# MCU.net
KiCad netlist of a schematic drawn in Altium Designer
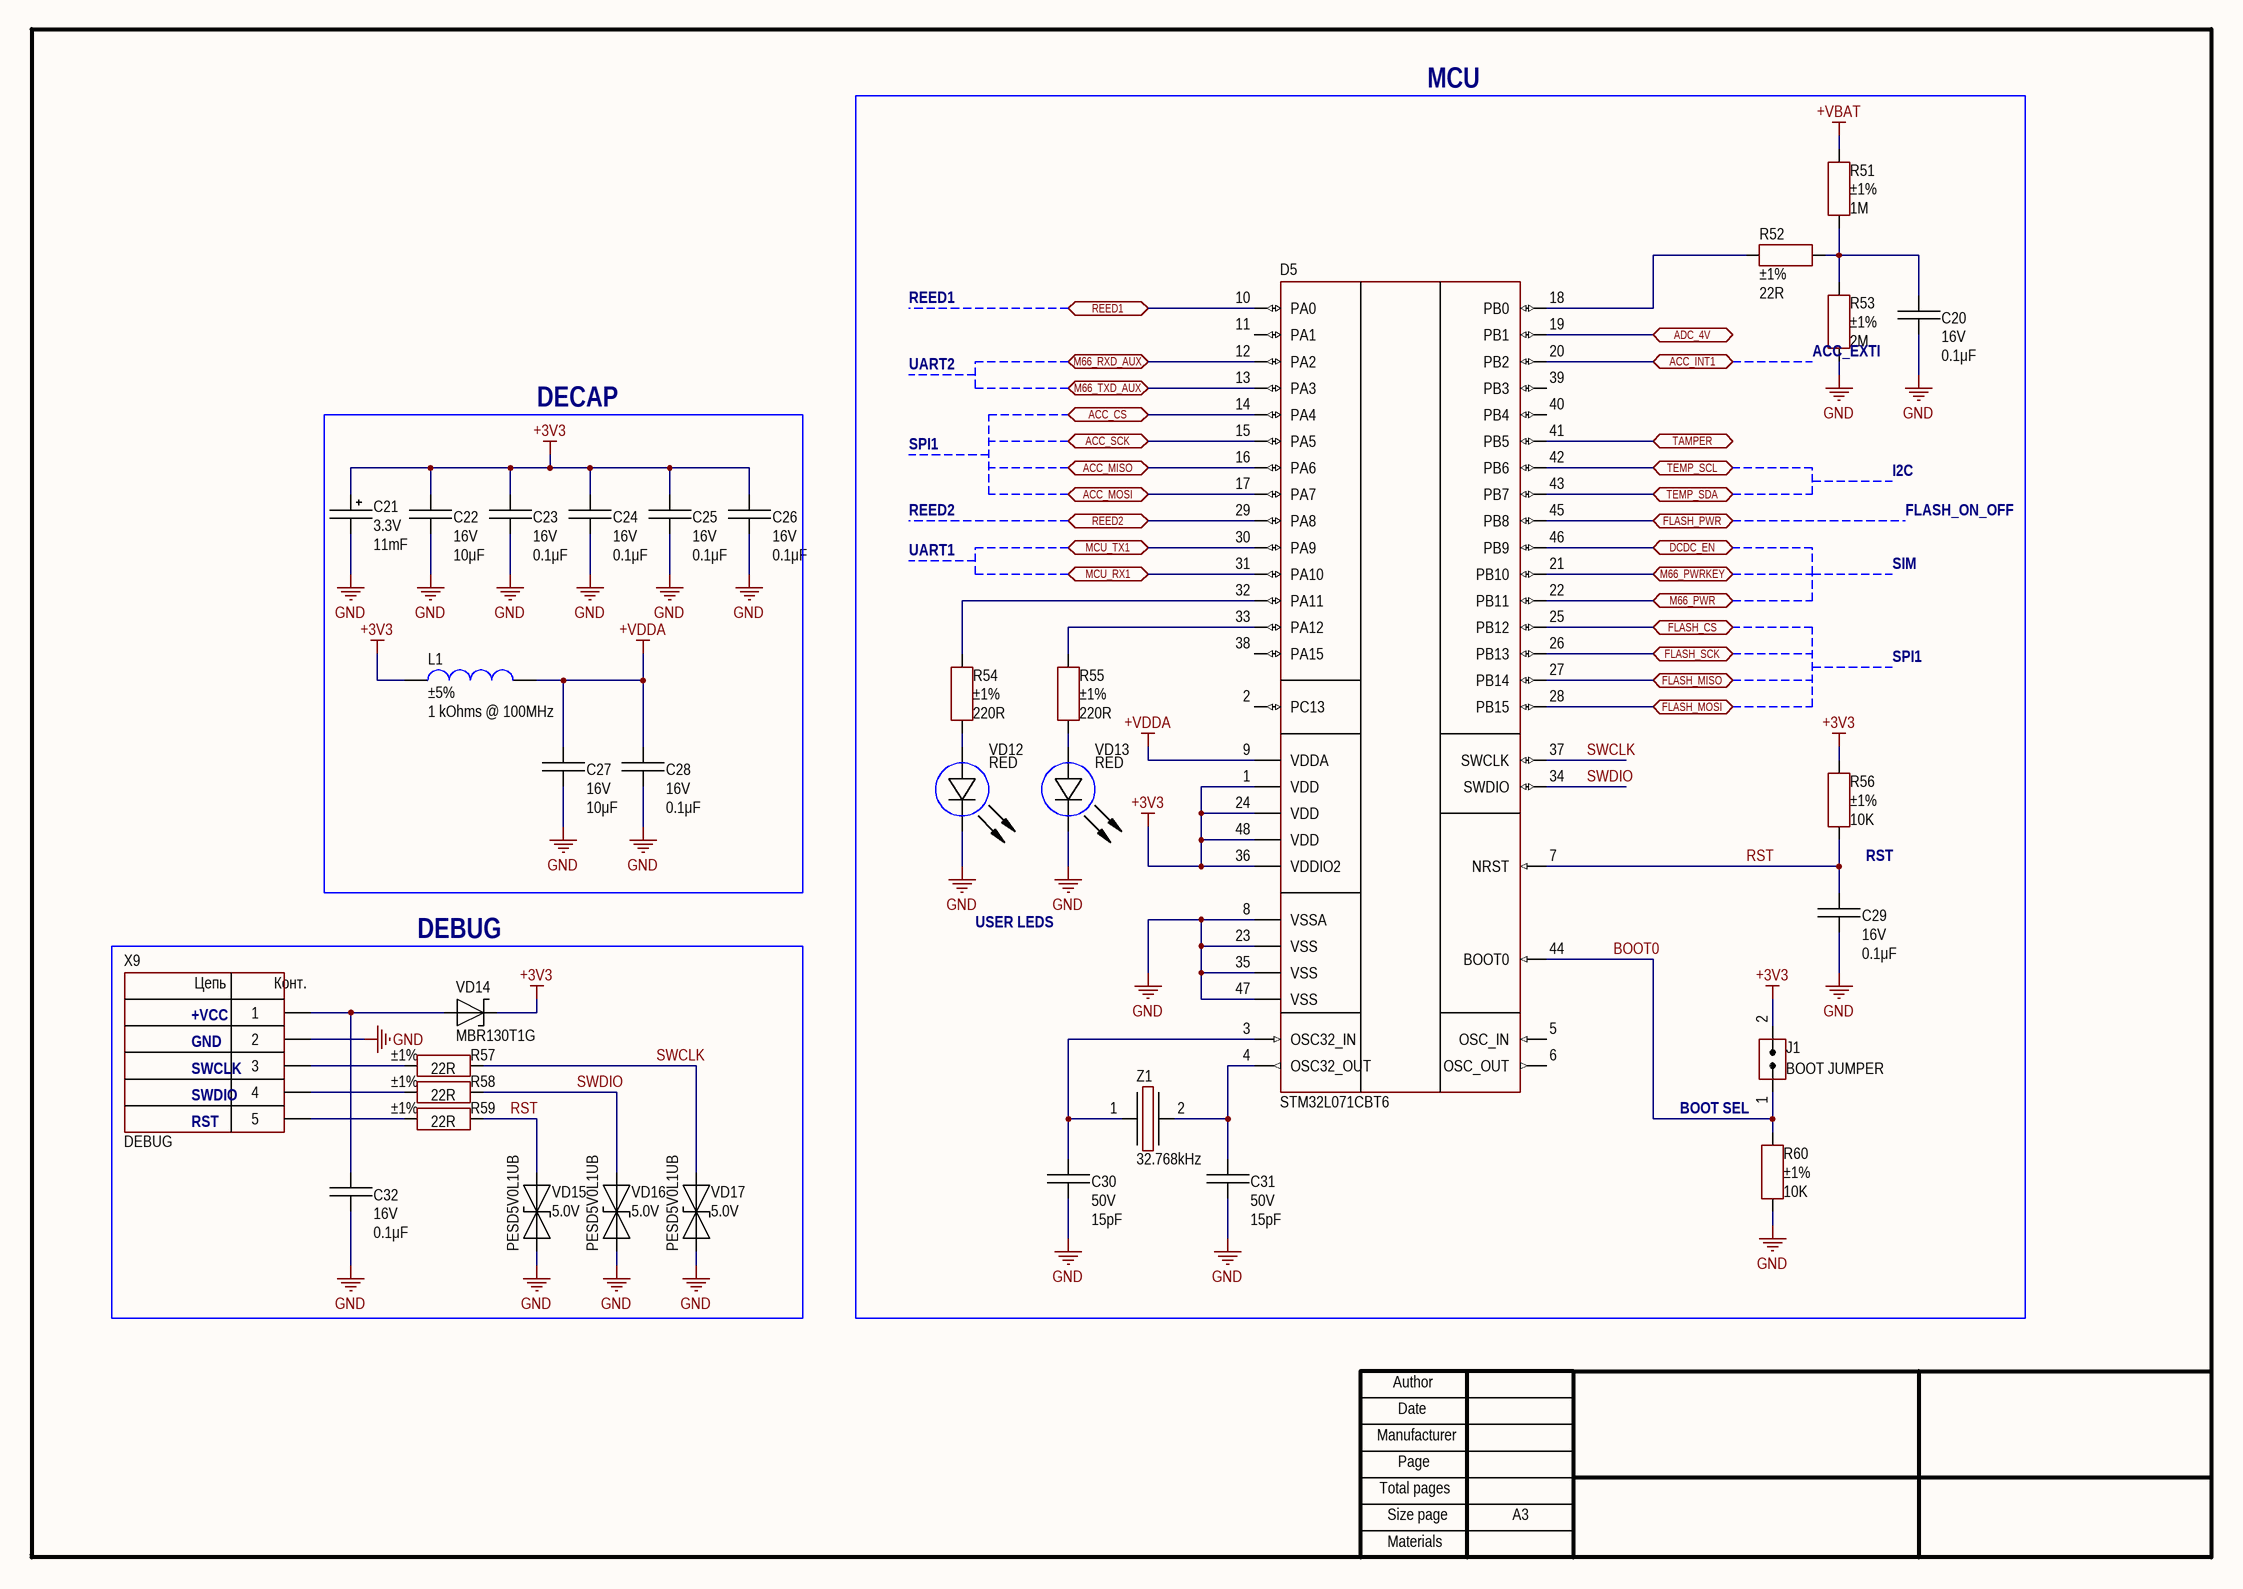
[diagram p0: MCU.SchDoc]

(export (version "E")
  (design (tool "Eeschema 10.0.6"))
  (components
    (comp (ref "C20")
      (value "0.1μF")
      (footprint "CAP: 0402")
      (description "±10% 16V Ceramic Capacitor X7R 0402 (1005 Metric)")
      (fields
        (field (name "MANUFACTURER") "Yageo")
        (field (name "PARTNUMBER") "CC0402KRX7R7BB104")
        (field (name "VOLTAGE") "16V")
      )
      (libsource (lib "capacitor") (part "Ceramic_0402"))
    )
    (comp (ref "C21")
      (value "11mF")
      (footprint "CAP: CPH3225A")
      (description "EDLC")
      (fields
        (field (name "MANUFACTURER") "Seiko Instruments")
        (field (name "PARTNUMBER") "F930J107KAAAJ6")
        (field (name "VOLTAGE") "3.3V")
      )
      (libsource (lib "MyLib") (part "CPH3225A"))
    )
    (comp (ref "C22")
      (value "10μF")
      (footprint "CAP: 0805")
      (description "±20% 16V Ceramic Capacitor X7R 0805 (2012 Metric)")
      (fields
        (field (name "MANUFACTURER") "Yageo")
        (field (name "PARTNUMBER") "CC0805MKX7R7BB106")
        (field (name "VOLTAGE") "16V")
      )
      (libsource (lib "capacitor") (part "Ceramic_0805"))
    )
    (comp (ref "C23")
      (value "0.1μF")
      (footprint "CAP: 0402")
      (description "±10% 16V Ceramic Capacitor X7R 0402 (1005 Metric)")
      (fields
        (field (name "MANUFACTURER") "Yageo")
        (field (name "PARTNUMBER") "CC0402KRX7R7BB104")
        (field (name "VOLTAGE") "16V")
      )
      (libsource (lib "capacitor") (part "Ceramic_0402"))
    )
    (comp (ref "C24")
      (value "0.1μF")
      (footprint "CAP: 0402")
      (description "±10% 16V Ceramic Capacitor X7R 0402 (1005 Metric)")
      (fields
        (field (name "MANUFACTURER") "Yageo")
        (field (name "PARTNUMBER") "CC0402KRX7R7BB104")
        (field (name "VOLTAGE") "16V")
      )
      (libsource (lib "capacitor") (part "Ceramic_0402"))
    )
    (comp (ref "C25")
      (value "0.1μF")
      (footprint "CAP: 0402")
      (description "±10% 16V Ceramic Capacitor X7R 0402 (1005 Metric)")
      (fields
        (field (name "MANUFACTURER") "Yageo")
        (field (name "PARTNUMBER") "CC0402KRX7R7BB104")
        (field (name "VOLTAGE") "16V")
      )
      (libsource (lib "capacitor") (part "Ceramic_0402"))
    )
    (comp (ref "C26")
      (value "0.1μF")
      (footprint "CAP: 0402")
      (description "±10% 16V Ceramic Capacitor X7R 0402 (1005 Metric)")
      (fields
        (field (name "MANUFACTURER") "Yageo")
        (field (name "PARTNUMBER") "CC0402KRX7R7BB104")
        (field (name "VOLTAGE") "16V")
      )
      (libsource (lib "capacitor") (part "Ceramic_0402"))
    )
    (comp (ref "C27")
      (value "10μF")
      (footprint "CAP: 0805")
      (description "±20% 16V Ceramic Capacitor X7R 0805 (2012 Metric)")
      (fields
        (field (name "MANUFACTURER") "Yageo")
        (field (name "PARTNUMBER") "CC0805MKX7R7BB106")
        (field (name "VOLTAGE") "16V")
      )
      (libsource (lib "capacitor") (part "Ceramic_0805"))
    )
    (comp (ref "C28")
      (value "0.1μF")
      (footprint "CAP: 0402")
      (description "±10% 16V Ceramic Capacitor X7R 0402 (1005 Metric)")
      (fields
        (field (name "MANUFACTURER") "Yageo")
        (field (name "PARTNUMBER") "CC0402KRX7R7BB104")
        (field (name "VOLTAGE") "16V")
      )
      (libsource (lib "capacitor") (part "Ceramic_0402"))
    )
    (comp (ref "C29")
      (value "0.1μF")
      (footprint "CAP: 0402")
      (description "±10% 16V Ceramic Capacitor X7R 0402 (1005 Metric)")
      (fields
        (field (name "MANUFACTURER") "Yageo")
        (field (name "PARTNUMBER") "CC0402KRX7R7BB104")
        (field (name "VOLTAGE") "16V")
      )
      (libsource (lib "capacitor") (part "Ceramic_0402"))
    )
    (comp (ref "C30")
      (value "15pF")
      (footprint "CAP: 0402")
      (description "±5% 50V Ceramic Capacitor C0G, NP0 0402 (1005 Metric)")
      (fields
        (field (name "MANUFACTURER") "Yageo")
        (field (name "PARTNUMBER") "CC0402JRNPO9BN150")
        (field (name "VOLTAGE") "50V")
      )
      (libsource (lib "capacitor") (part "Ceramic_0402"))
    )
    (comp (ref "C31")
      (value "15pF")
      (footprint "CAP: 0402")
      (description "±5% 50V Ceramic Capacitor C0G, NP0 0402 (1005 Metric)")
      (fields
        (field (name "MANUFACTURER") "Yageo")
        (field (name "PARTNUMBER") "CC0402JRNPO9BN150")
        (field (name "VOLTAGE") "50V")
      )
      (libsource (lib "capacitor") (part "Ceramic_0402"))
    )
    (comp (ref "C32")
      (value "0.1μF")
      (footprint "CAP: 0402")
      (description "±10% 16V Ceramic Capacitor X7R 0402 (1005 Metric)")
      (fields
        (field (name "MANUFACTURER") "Yageo")
        (field (name "PARTNUMBER") "CC0402KRX7R7BB104")
        (field (name "VOLTAGE") "16V")
      )
      (libsource (lib "capacitor") (part "Ceramic_0402"))
    )
    (comp (ref "D5")
      (value "~")
      (footprint "48-LQFP")
      (description "ARM® Cortex®-M0+ series Microcontroller IC 32-Bit 32MHz 128KB (128K x 8) FLASH 48-LQFP (7x7)")
      (fields
        (field (name "MANUFACTURER") "STMicroelectronics")
        (field (name "VALUEMANUFACTURERPARTNUMBER") "IC microcontroller, 32-Bit, Cortex-M0+, 32MHz, 128KB, 20KB, 1.65V...3.6V, -40...+85°C, 48-LQFP")
        (field (name "PARTNUMBER") "STM32L071CBT6")
      )
      (libsource (lib "MyLib") (part "STM32L071C8T6"))
    )
    (comp (ref "J1")
      (value "~")
      (footprint "CON: JUMPER x1")
      (fields (field (name "COMMENTTEXT") "BOOT JUMPER"))
      (libsource (lib "connector") (part "Jumper_single"))
    )
    (comp (ref "L1")
      (value "1 kOhms @ 100MHz")
      (footprint "IND: 0402")
      (description "100 nH Unshielded Multilayer Inductor 200 mA 1.25Ohm Max 0402 (1005 Metric)")
      (fields
        (field (name "MANUFACTURER") "Murata Electronics")
        (field (name "PARTNUMBER") "LQG15HSR10J02D")
        (field (name "TOLERANCE") "±5%")
      )
      (libsource (lib "inductor") (part "Inductor_0402"))
    )
    (comp (ref "R51")
      (value "1M")
      (footprint "RES: 0402")
      (description "1 MOhms ±1% 0.063W, 1/16W Chip Resistor 0402 (1005 Metric) Moisture Resistant Thick Film")
      (fields
        (field (name "MANUFACTURER") "Yageo")
        (field (name "PARTNUMBER") "RC0402FR-071ML")
        (field (name "TOLERANCE") "±1%")
      )
      (libsource (lib "resistor") (part "Resistor_0402"))
    )
    (comp (ref "R52")
      (value "22R")
      (footprint "RES: 0402")
      (description "22 Ohms ±1% 0.063W, 1/16W Chip Resistor 0402 (1005 Metric) Moisture Resistant Thick Film")
      (fields
        (field (name "MANUFACTURER") "Yageo")
        (field (name "PARTNUMBER") "RC0402FR-0722RL")
        (field (name "TOLERANCE") "±1%")
      )
      (libsource (lib "resistor") (part "Resistor_0402"))
    )
    (comp (ref "R53")
      (value "2M")
      (footprint "RES: 0402")
      (description "2 MOhms ±1% 0.063W, 1/16W Chip Resistor 0402 (1005 Metric) Moisture Resistant Thick Film")
      (fields
        (field (name "MANUFACTURER") "Yageo")
        (field (name "PARTNUMBER") "RC0402FR-072ML")
        (field (name "TOLERANCE") "±1%")
      )
      (libsource (lib "resistor") (part "Resistor_0402"))
    )
    (comp (ref "R54")
      (value "220R")
      (footprint "RES: 0402")
      (description "220 Ohms ±1% 0.063W, 1/16W Chip Resistor 0402 (1005 Metric) Moisture Resistant Thick Film")
      (fields
        (field (name "MANUFACTURER") "Yageo")
        (field (name "PARTNUMBER") "RC0402FR-07220RL")
        (field (name "TOLERANCE") "±1%")
      )
      (libsource (lib "") (part "Resistor_0402_1"))
    )
    (comp (ref "R55")
      (value "220R")
      (footprint "RES: 0402")
      (description "220 Ohms ±1% 0.063W, 1/16W Chip Resistor 0402 (1005 Metric) Moisture Resistant Thick Film")
      (fields
        (field (name "MANUFACTURER") "Yageo")
        (field (name "PARTNUMBER") "RC0402FR-07220RL")
        (field (name "TOLERANCE") "±1%")
      )
      (libsource (lib "") (part "Resistor_0402_1"))
    )
    (comp (ref "R56")
      (value "10K")
      (footprint "RES: 0402")
      (description "10 kOhms ±1% 0.063W, 1/16W Chip Resistor 0402 (1005 Metric) Moisture Resistant Thick Film")
      (fields
        (field (name "MANUFACTURER") "Yageo")
        (field (name "PARTNUMBER") "RC0402FR-0710KL")
        (field (name "TOLERANCE") "±1%")
      )
      (libsource (lib "resistor") (part "Resistor_0402"))
    )
    (comp (ref "R57")
      (value "22R")
      (footprint "RES: 0402")
      (description "22 Ohms ±1% 0.063W, 1/16W Chip Resistor 0402 (1005 Metric) Moisture Resistant Thick Film")
      (fields
        (field (name "MANUFACTURER") "Yageo")
        (field (name "PARTNUMBER") "RC0402FR-0722RL")
        (field (name "TOLERANCE") "±1%")
      )
      (libsource (lib "resistor") (part "Resistor_0402"))
    )
    (comp (ref "R58")
      (value "22R")
      (footprint "RES: 0402")
      (description "22 Ohms ±1% 0.063W, 1/16W Chip Resistor 0402 (1005 Metric) Moisture Resistant Thick Film")
      (fields
        (field (name "MANUFACTURER") "Yageo")
        (field (name "PARTNUMBER") "RC0402FR-0722RL")
        (field (name "TOLERANCE") "±1%")
      )
      (libsource (lib "resistor") (part "Resistor_0402"))
    )
    (comp (ref "R59")
      (value "22R")
      (footprint "RES: 0402")
      (description "22 Ohms ±1% 0.063W, 1/16W Chip Resistor 0402 (1005 Metric) Moisture Resistant Thick Film")
      (fields
        (field (name "MANUFACTURER") "Yageo")
        (field (name "PARTNUMBER") "RC0402FR-0722RL")
        (field (name "TOLERANCE") "±1%")
      )
      (libsource (lib "resistor") (part "Resistor_0402"))
    )
    (comp (ref "R60")
      (value "10K")
      (footprint "RES: 0402")
      (description "10 kOhms ±1% 0.063W, 1/16W Chip Resistor 0402 (1005 Metric) Moisture Resistant Thick Film")
      (fields
        (field (name "MANUFACTURER") "Yageo")
        (field (name "PARTNUMBER") "RC0402FR-0710KL")
        (field (name "TOLERANCE") "±1%")
      )
      (libsource (lib "resistor") (part "Resistor_0402"))
    )
    (comp (ref "VD12")
      (value "~")
      (footprint "LED: 0805R")
      (description "Red 625nm LED Indication - Discrete 1.8V 0805 (2012 Metric)")
      (fields
        (field (name "MANUFACTURER") "Kingbright")
        (field (name "VALUEMANUFACTURERPARTNUMBER") "LED, RED, 30mA, 1.8V, 0805, -55...+150°C")
        (field (name "COLOR") "RED")
      )
      (libsource (lib "diode") (part "LED_single"))
    )
    (comp (ref "VD13")
      (value "~")
      (footprint "LED: 0805R")
      (description "Red 625nm LED Indication - Discrete 1.8V 0805 (2012 Metric)")
      (fields
        (field (name "MANUFACTURER") "Kingbright")
        (field (name "VALUEMANUFACTURERPARTNUMBER") "LED, RED, 30mA, 1.8V, 0805, -55...+150°C")
        (field (name "COLOR") "RED")
      )
      (libsource (lib "diode") (part "LED_single"))
    )
    (comp (ref "VD14")
      (value "~")
      (footprint "DIODE: SOD123")
      (description "Diode Schottky 30 V 1A Surface Mount SOD-123")
      (fields
        (field (name "MANUFACTURER") "Diodes Incorporated")
        (field (name "VALUEMANUFACTURERPARTNUMBER") "Schottky diode, 30V, 1A, 0.45V, 15pF, SOD-123, -55...+150°C")
        (field (name "PARTNUMBER") "MBR130T1G")
      )
      (libsource (lib "diode") (part "Schottky_single"))
    )
    (comp (ref "VD15")
      (value "~")
      (footprint "DIODE: SOD523")
      (description "12V Clamp 3.5A (8/20µs) Ipp Tvs Diode Surface Mount SOD-523")
      (fields
        (field (name "MANUFACTURER") "Nexperia")
        (field (name "VALUEMANUFACTURERPARTNUMBER") "ESD TVS diode, 5.0V, 3.5A, , , SOD-523, -55...+150°C")
        (field (name "VOLTAGE") "5.0V")
        (field (name "PARTNUMBER") "PESD5V0L1UB")
      )
      (libsource (lib "diode") (part "TVS_single"))
    )
    (comp (ref "VD16")
      (value "~")
      (footprint "DIODE: SOD523")
      (description "12V Clamp 3.5A (8/20µs) Ipp Tvs Diode Surface Mount SOD-523")
      (fields
        (field (name "MANUFACTURER") "Nexperia")
        (field (name "VALUEMANUFACTURERPARTNUMBER") "ESD TVS diode, 5.0V, 3.5A, , , SOD-523, -55...+150°C")
        (field (name "VOLTAGE") "5.0V")
        (field (name "PARTNUMBER") "PESD5V0L1UB")
      )
      (libsource (lib "diode") (part "TVS_single"))
    )
    (comp (ref "VD17")
      (value "~")
      (footprint "DIODE: SOD523")
      (description "12V Clamp 3.5A (8/20µs) Ipp Tvs Diode Surface Mount SOD-523")
      (fields
        (field (name "MANUFACTURER") "Nexperia")
        (field (name "VALUEMANUFACTURERPARTNUMBER") "ESD TVS diode, 5.0V, 3.5A, , , SOD-523, -55...+150°C")
        (field (name "VOLTAGE") "5.0V")
        (field (name "PARTNUMBER") "PESD5V0L1UB")
      )
      (libsource (lib "diode") (part "TVS_single"))
    )
    (comp (ref "X9")
      (value "~")
      (footprint "CON: PLS-5")
      (description "Pin Header 5 pin Straight, 2.54mm Through Hole.")
      (fields
        (field (name "MANUFACTURER") "KLS")
        (field (name "VALUEMANUFACTURERPARTNUMBER") "Connector, 5pin, 2.54mm, 500VAC, 0.1A")
        (field (name "COMMENTTEXT") "DEBUG")
      )
      (libsource (lib "connector") (part "PLS-5"))
    )
    (comp (ref "Z1")
      (value "~")
      (footprint "OSC: 3215")
      (description "3215 ±20ppm Crystal 12.5pF 2-SMD, No Lead")
      (fields
        (field (name "MANUFACTURER") "Epson")
        (field (name "PARTNUMBER") "FC-135 32.7680KA-A5")
        (field (name "FREQUENCY") "32.768kHz")
      )
      (libsource (lib "oscilator") (part "Crystal_3215"))
    )
  )
  (nets
    (net (code "1") (name "+3V3") (class "Default")
      (node (ref "C21") (pin "1") (pinfunction "1_1") (pintype "passive"))
      (node (ref "C22") (pin "2") (pinfunction "2_2") (pintype "passive"))
      (node (ref "C23") (pin "2") (pinfunction "2_2") (pintype "passive"))
      (node (ref "C24") (pin "2") (pinfunction "2_2") (pintype "passive"))
      (node (ref "C25") (pin "2") (pinfunction "2_2") (pintype "passive"))
      (node (ref "C26") (pin "2") (pinfunction "2_2") (pintype "passive"))
      (node (ref "D5") (pin "1") (pinfunction "VDD_1") (pintype "power_in"))
      (node (ref "D5") (pin "24") (pinfunction "VDD_24") (pintype "power_in"))
      (node (ref "D5") (pin "36") (pinfunction "VDDIO2_36") (pintype "power_in"))
      (node (ref "D5") (pin "48") (pinfunction "VDD_48") (pintype "power_in"))
      (node (ref "J1") (pin "2") (pinfunction "IN_2") (pintype "passive"))
      (node (ref "L1") (pin "2") (pinfunction "2_2") (pintype "passive"))
      (node (ref "R56") (pin "2") (pinfunction "2_2") (pintype "passive"))
      (node (ref "VD14") (pin "2") (pinfunction "2_2") (pintype "passive"))
    )
    (net (code "2") (name "+VBAT") (class "Default")
      (node (ref "R51") (pin "2") (pinfunction "2_2") (pintype "passive"))
    )
    (net (code "3") (name "+VDDA") (class "Default")
      (node (ref "C27") (pin "2") (pinfunction "2_2") (pintype "passive"))
      (node (ref "C28") (pin "2") (pinfunction "2_2") (pintype "passive"))
      (node (ref "D5") (pin "9") (pinfunction "VDDA_9") (pintype "power_in"))
      (node (ref "L1") (pin "1") (pinfunction "1_1") (pintype "passive"))
    )
    (net (code "4") (name "/ACC_CS") (class "Default")
      (node (ref "D5") (pin "14") (pinfunction "PA4_14") (pintype "bidirectional"))
    )
    (net (code "5") (name "/ACC_INT1") (class "Default")
      (node (ref "D5") (pin "20") (pinfunction "PB2_20") (pintype "bidirectional"))
    )
    (net (code "6") (name "/ACC_MISO") (class "Default")
      (node (ref "D5") (pin "16") (pinfunction "PA6_16") (pintype "bidirectional"))
    )
    (net (code "7") (name "/ACC_MOSI") (class "Default")
      (node (ref "D5") (pin "17") (pinfunction "PA7_17") (pintype "bidirectional"))
    )
    (net (code "8") (name "/ACC_SCK") (class "Default")
      (node (ref "D5") (pin "15") (pinfunction "PA5_15") (pintype "bidirectional"))
    )
    (net (code "9") (name "/ADC_4V") (class "Default")
      (node (ref "D5") (pin "19") (pinfunction "PB1_19") (pintype "bidirectional"))
    )
    (net (code "10") (name "/BOOT0") (class "Default")
      (node (ref "D5") (pin "44") (pinfunction "BOOT0_44") (pintype "input"))
      (node (ref "J1") (pin "1") (pinfunction "IN_1") (pintype "passive"))
      (node (ref "R60") (pin "2") (pinfunction "2_2") (pintype "passive"))
    )
    (net (code "11") (name "/DCDC_EN") (class "Default")
      (node (ref "D5") (pin "46") (pinfunction "PB9_46") (pintype "bidirectional"))
    )
    (net (code "12") (name "/FLASH_CS") (class "Default")
      (node (ref "D5") (pin "25") (pinfunction "PB12_25") (pintype "bidirectional"))
    )
    (net (code "13") (name "/FLASH_MISO") (class "Default")
      (node (ref "D5") (pin "27") (pinfunction "PB14_27") (pintype "bidirectional"))
    )
    (net (code "14") (name "/FLASH_MOSI") (class "Default")
      (node (ref "D5") (pin "28") (pinfunction "PB15_28") (pintype "bidirectional"))
    )
    (net (code "15") (name "/FLASH_PWR") (class "Default")
      (node (ref "D5") (pin "45") (pinfunction "PB8_45") (pintype "bidirectional"))
    )
    (net (code "16") (name "/FLASH_SCK") (class "Default")
      (node (ref "D5") (pin "26") (pinfunction "PB13_26") (pintype "bidirectional"))
    )
    (net (code "17") (name "/M66_PWR") (class "Default")
      (node (ref "D5") (pin "22") (pinfunction "PB11_22") (pintype "bidirectional"))
    )
    (net (code "18") (name "/M66_PWRKEY") (class "Default")
      (node (ref "D5") (pin "21") (pinfunction "PB10_21") (pintype "bidirectional"))
    )
    (net (code "19") (name "/M66_RXD_AUX") (class "Default")
      (node (ref "D5") (pin "12") (pinfunction "PA2_12") (pintype "bidirectional"))
    )
    (net (code "20") (name "/M66_TXD_AUX") (class "Default")
      (node (ref "D5") (pin "13") (pinfunction "PA3_13") (pintype "bidirectional"))
    )
    (net (code "21") (name "/MCU_RX1") (class "Default")
      (node (ref "D5") (pin "31") (pinfunction "PA10_31") (pintype "bidirectional"))
    )
    (net (code "22") (name "/MCU_TX1") (class "Default")
      (node (ref "D5") (pin "30") (pinfunction "PA9_30") (pintype "bidirectional"))
    )
    (net (code "23") (name "/REED1") (class "Default")
      (node (ref "D5") (pin "10") (pinfunction "PA0_10") (pintype "bidirectional"))
    )
    (net (code "24") (name "/REED2") (class "Default")
      (node (ref "D5") (pin "29") (pinfunction "PA8_29") (pintype "bidirectional"))
    )
    (net (code "25") (name "/RST") (class "Default")
      (node (ref "C29") (pin "2") (pinfunction "2_2") (pintype "passive"))
      (node (ref "D5") (pin "7") (pinfunction "NRST_7") (pintype "input"))
      (node (ref "R56") (pin "1") (pinfunction "1_1") (pintype "passive"))
      (node (ref "R59") (pin "2") (pinfunction "2_2") (pintype "passive"))
      (node (ref "VD15") (pin "2") (pinfunction "C_2") (pintype "passive"))
    )
    (net (code "26") (name "/SWCLK") (class "Default")
      (node (ref "D5") (pin "37") (pinfunction "SWCLK_37") (pintype "bidirectional"))
      (node (ref "R57") (pin "2") (pinfunction "2_2") (pintype "passive"))
      (node (ref "VD17") (pin "2") (pinfunction "C_2") (pintype "passive"))
    )
    (net (code "27") (name "/SWDIO") (class "Default")
      (node (ref "D5") (pin "34") (pinfunction "SWDIO_34") (pintype "bidirectional"))
      (node (ref "R58") (pin "2") (pinfunction "2_2") (pintype "passive"))
      (node (ref "VD16") (pin "2") (pinfunction "C_2") (pintype "passive"))
    )
    (net (code "28") (name "/TAMPER") (class "Default")
      (node (ref "D5") (pin "41") (pinfunction "PB5_41") (pintype "bidirectional"))
    )
    (net (code "29") (name "/TEMP_SCL") (class "Default")
      (node (ref "D5") (pin "42") (pinfunction "PB6_42") (pintype "bidirectional"))
    )
    (net (code "30") (name "/TEMP_SDA") (class "Default")
      (node (ref "D5") (pin "43") (pinfunction "PB7_43") (pintype "bidirectional"))
    )
    (net (code "31") (name "GND") (class "Default")
      (node (ref "C20") (pin "1") (pinfunction "1_1") (pintype "passive"))
      (node (ref "C21") (pin "2") (pinfunction "2_2") (pintype "passive"))
      (node (ref "C22") (pin "1") (pinfunction "1_1") (pintype "passive"))
      (node (ref "C23") (pin "1") (pinfunction "1_1") (pintype "passive"))
      (node (ref "C24") (pin "1") (pinfunction "1_1") (pintype "passive"))
      (node (ref "C25") (pin "1") (pinfunction "1_1") (pintype "passive"))
      (node (ref "C26") (pin "1") (pinfunction "1_1") (pintype "passive"))
      (node (ref "C27") (pin "1") (pinfunction "1_1") (pintype "passive"))
      (node (ref "C28") (pin "1") (pinfunction "1_1") (pintype "passive"))
      (node (ref "C29") (pin "1") (pinfunction "1_1") (pintype "passive"))
      (node (ref "C30") (pin "1") (pinfunction "1_1") (pintype "passive"))
      (node (ref "C31") (pin "1") (pinfunction "1_1") (pintype "passive"))
      (node (ref "C32") (pin "1") (pinfunction "1_1") (pintype "passive"))
      (node (ref "D5") (pin "23") (pinfunction "VSS_23") (pintype "power_in"))
      (node (ref "D5") (pin "35") (pinfunction "VSS_35") (pintype "power_in"))
      (node (ref "D5") (pin "47") (pinfunction "VSS_47") (pintype "power_in"))
      (node (ref "D5") (pin "8") (pinfunction "VSSA_8") (pintype "power_in"))
      (node (ref "R53") (pin "1") (pinfunction "1_1") (pintype "passive"))
      (node (ref "R60") (pin "1") (pinfunction "1_1") (pintype "passive"))
      (node (ref "VD12") (pin "2") (pinfunction "C_2") (pintype "passive"))
      (node (ref "VD13") (pin "2") (pinfunction "C_2") (pintype "passive"))
      (node (ref "VD15") (pin "1") (pinfunction "A_1") (pintype "passive"))
      (node (ref "VD16") (pin "1") (pinfunction "A_1") (pintype "passive"))
      (node (ref "VD17") (pin "1") (pinfunction "A_1") (pintype "passive"))
      (node (ref "X9") (pin "2") (pinfunction "2_2") (pintype "passive"))
    )
    (net (code "32") (name "Net-(C20-Pad2)") (class "Default")
      (node (ref "C20") (pin "2") (pinfunction "2_2") (pintype "passive"))
      (node (ref "R51") (pin "1") (pinfunction "1_1") (pintype "passive"))
      (node (ref "R52") (pin "2") (pinfunction "2_2") (pintype "passive"))
      (node (ref "R53") (pin "2") (pinfunction "2_2") (pintype "passive"))
    )
    (net (code "33") (name "Net-(C32-Pad2)") (class "Default")
      (node (ref "C32") (pin "2") (pinfunction "2_2") (pintype "passive"))
      (node (ref "VD14") (pin "1") (pinfunction "1_1") (pintype "passive"))
      (node (ref "X9") (pin "1") (pinfunction "1_1") (pintype "passive"))
    )
    (net (code "34") (name "Net-(D5-OSC32_IN)") (class "Default")
      (node (ref "C30") (pin "2") (pinfunction "2_2") (pintype "passive"))
      (node (ref "D5") (pin "3") (pinfunction "OSC32_IN_3") (pintype "input"))
      (node (ref "Z1") (pin "1") (pinfunction "1_1") (pintype "passive"))
    )
    (net (code "35") (name "Net-(D5-OSC32_OUT)") (class "Default")
      (node (ref "C31") (pin "2") (pinfunction "2_2") (pintype "passive"))
      (node (ref "D5") (pin "4") (pinfunction "OSC32_OUT_4") (pintype "output"))
      (node (ref "Z1") (pin "2") (pinfunction "2_2") (pintype "passive"))
    )
    (net (code "36") (name "Net-(D5-PA11)") (class "Default")
      (node (ref "D5") (pin "32") (pinfunction "PA11_32") (pintype "bidirectional"))
      (node (ref "R54") (pin "2") (pinfunction "2_2") (pintype "passive"))
    )
    (net (code "37") (name "Net-(D5-PA12)") (class "Default")
      (node (ref "D5") (pin "33") (pinfunction "PA12_33") (pintype "bidirectional"))
      (node (ref "R55") (pin "2") (pinfunction "2_2") (pintype "passive"))
    )
    (net (code "38") (name "Net-(D5-PB0)") (class "Default")
      (node (ref "D5") (pin "18") (pinfunction "PB0_18") (pintype "bidirectional"))
      (node (ref "R52") (pin "1") (pinfunction "1_1") (pintype "passive"))
    )
    (net (code "39") (name "Net-(R57-Pad1)") (class "Default")
      (node (ref "R57") (pin "1") (pinfunction "1_1") (pintype "passive"))
      (node (ref "X9") (pin "3") (pinfunction "3_3") (pintype "power_in"))
    )
    (net (code "40") (name "Net-(R58-Pad1)") (class "Default")
      (node (ref "R58") (pin "1") (pinfunction "1_1") (pintype "passive"))
      (node (ref "X9") (pin "4") (pinfunction "4_4") (pintype "power_in"))
    )
    (net (code "41") (name "Net-(R59-Pad1)") (class "Default")
      (node (ref "R59") (pin "1") (pinfunction "1_1") (pintype "passive"))
      (node (ref "X9") (pin "5") (pinfunction "5_5") (pintype "power_in"))
    )
    (net (code "42") (name "Net-(VD12-A)") (class "Default")
      (node (ref "R54") (pin "1") (pinfunction "1_1") (pintype "passive"))
      (node (ref "VD12") (pin "1") (pinfunction "A_1") (pintype "passive"))
    )
    (net (code "43") (name "Net-(VD13-A)") (class "Default")
      (node (ref "R55") (pin "1") (pinfunction "1_1") (pintype "passive"))
      (node (ref "VD13") (pin "1") (pinfunction "A_1") (pintype "passive"))
    )
    (net (code "44") (name "unconnected-(D5-OSC_IN-Pad5)") (class "Default")
      (node (ref "D5") (pin "5") (pinfunction "OSC_IN_5") (pintype "input"))
    )
    (net (code "45") (name "unconnected-(D5-OSC_OUT-Pad6)") (class "Default")
      (node (ref "D5") (pin "6") (pinfunction "OSC_OUT_6") (pintype "output"))
    )
    (net (code "46") (name "unconnected-(D5-PA1-Pad11)") (class "Default")
      (node (ref "D5") (pin "11") (pinfunction "PA1_11") (pintype "bidirectional"))
    )
    (net (code "47") (name "unconnected-(D5-PA15-Pad38)") (class "Default")
      (node (ref "D5") (pin "38") (pinfunction "PA15_38") (pintype "bidirectional"))
    )
    (net (code "48") (name "unconnected-(D5-PB3-Pad39)") (class "Default")
      (node (ref "D5") (pin "39") (pinfunction "PB3_39") (pintype "bidirectional"))
    )
    (net (code "49") (name "unconnected-(D5-PB4-Pad40)") (class "Default")
      (node (ref "D5") (pin "40") (pinfunction "PB4_40") (pintype "bidirectional"))
    )
    (net (code "50") (name "unconnected-(D5-PC13-Pad2)") (class "Default")
      (node (ref "D5") (pin "2") (pinfunction "PC13_2") (pintype "bidirectional"))
    )
  )
)
